# epic2.net
KiCad netlist of a schematic drawn in EAGLE
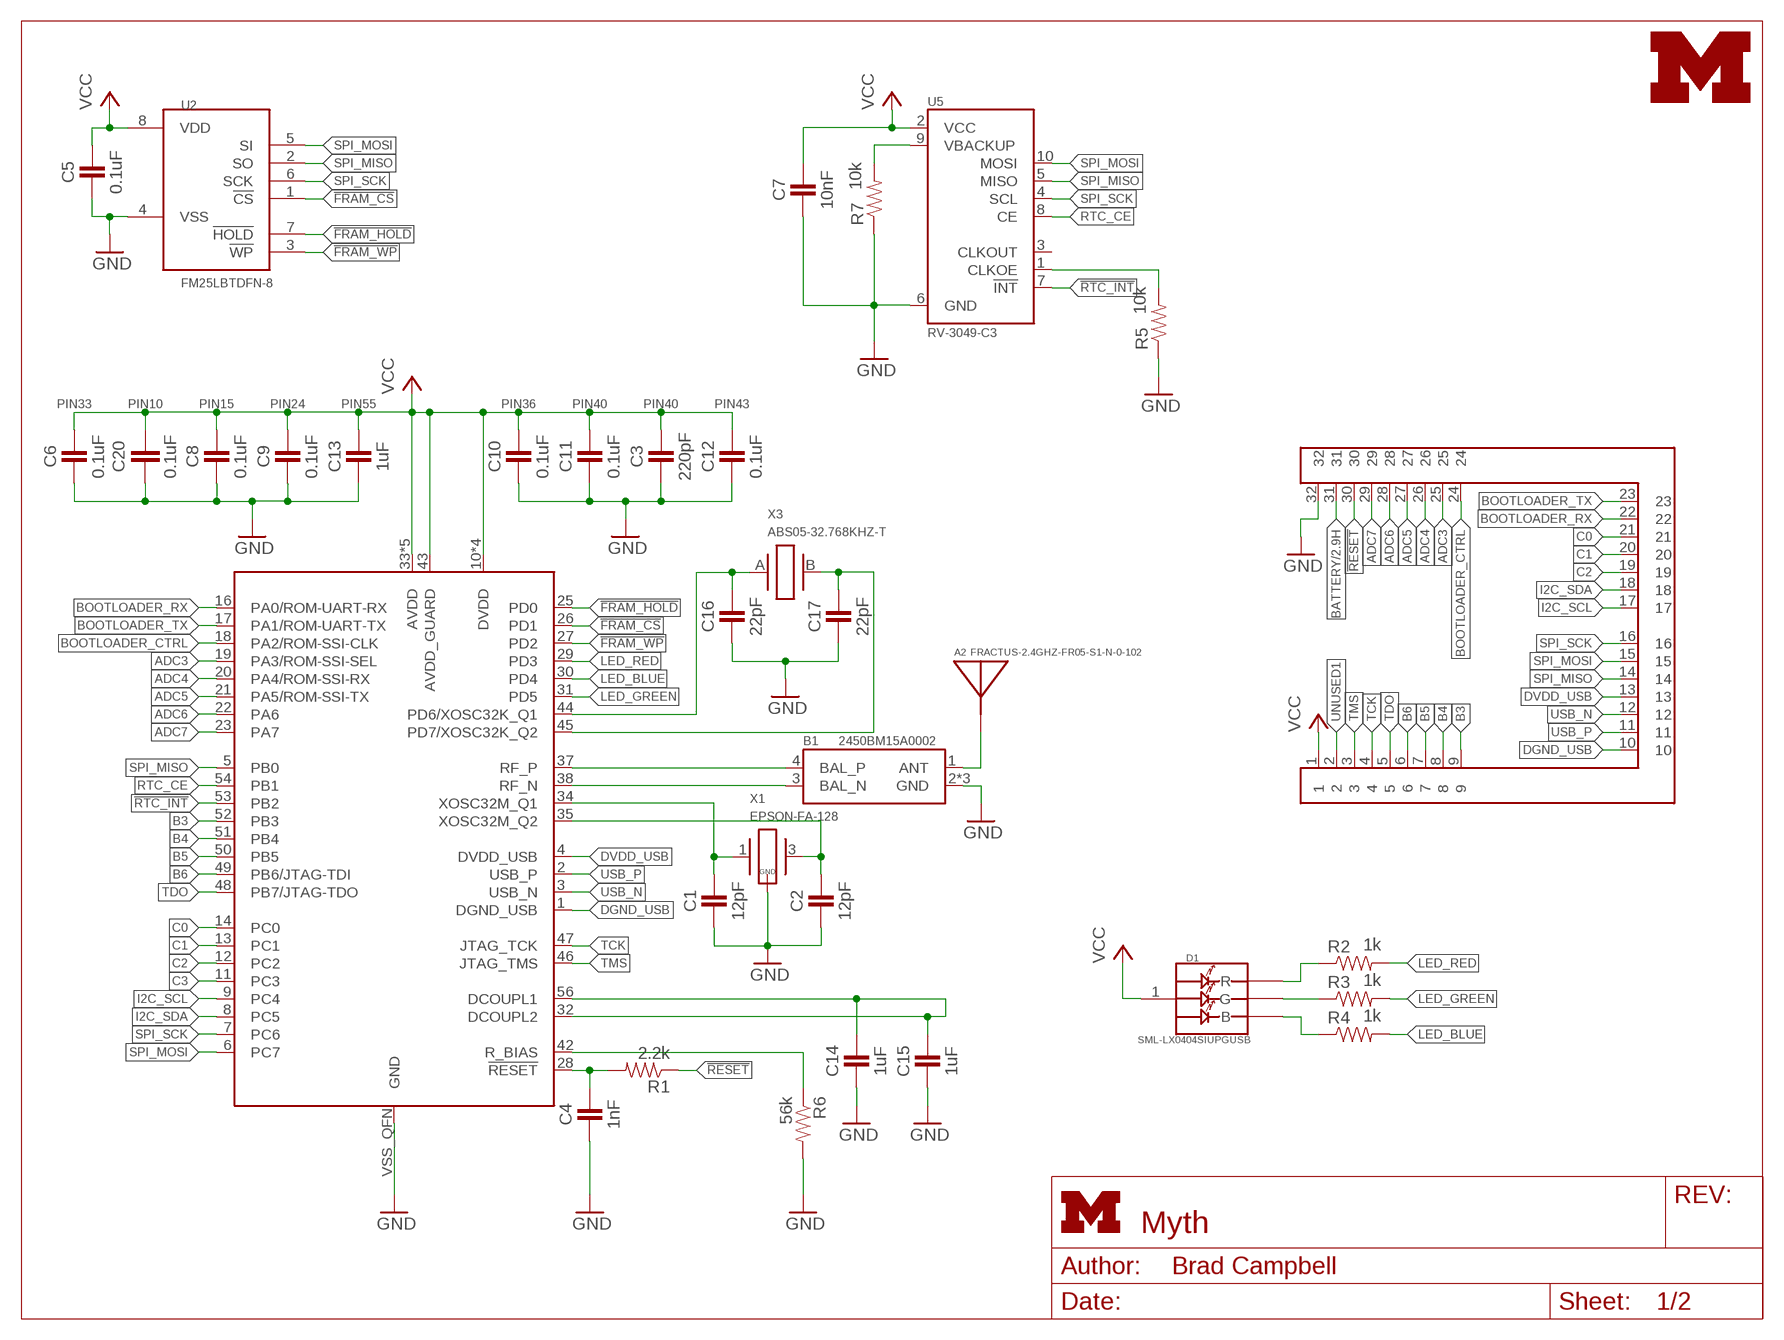
[diagram p0: schematic, sheet 1]
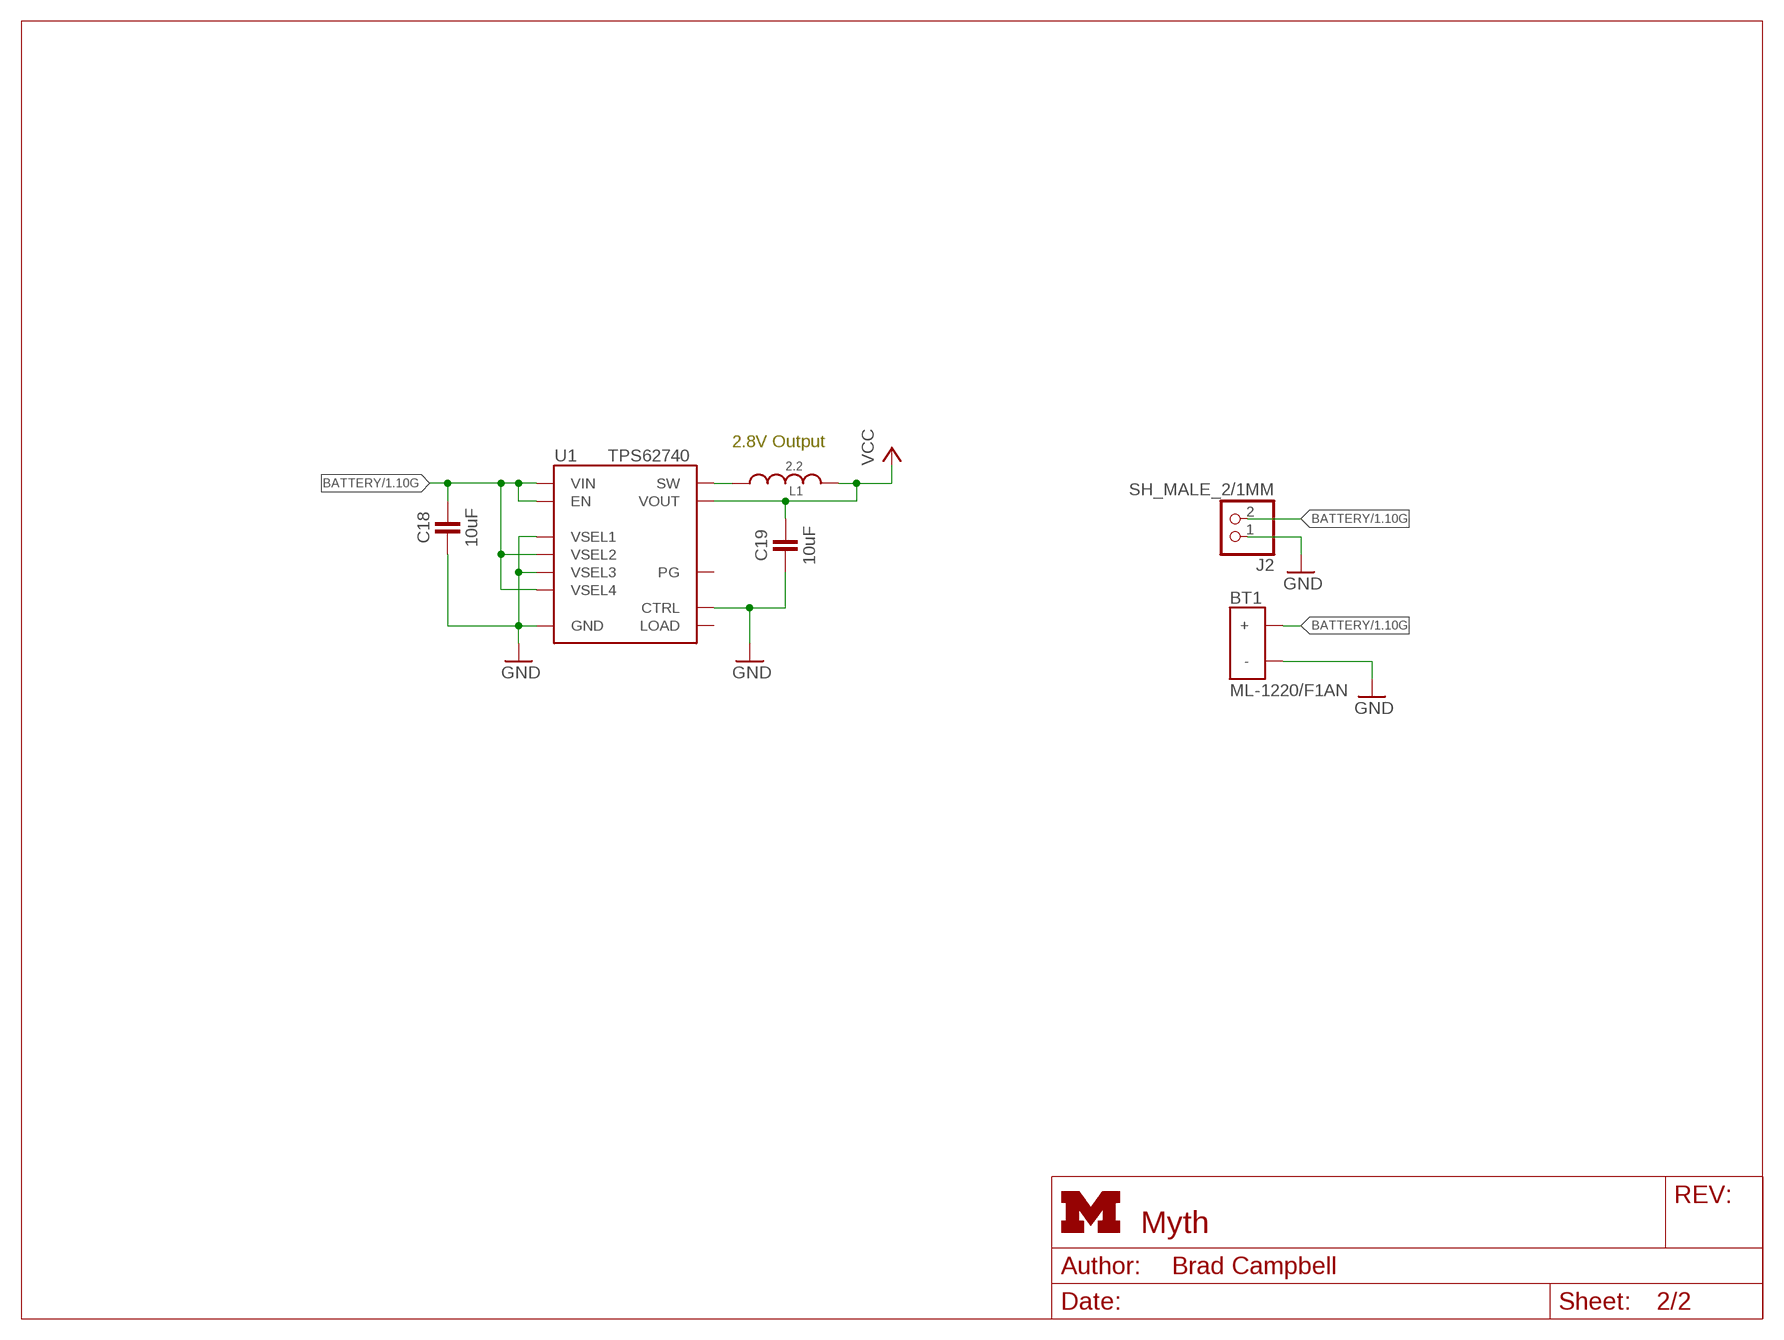
[diagram p1: schematic, sheet 2]

(export (version "E")
  (design (tool "Eeschema 10.0.6"))
  (components
    (comp (ref "A2")
      (value "FRACTUS-2.4GHZ-FR05-S1-N-0-102")
      (footprint "eagle-import:FRACTUS-ANTENNA-FR05-S1-N-0-102")
      (libsource (lib "eagle-import") (part "FRACTUS-2.4GHZ-FR05-S1-N-0-102"))
    )
    (comp (ref "B1")
      (value "2450BM15A0002")
      (footprint "eagle-import:2450BM")
      (libsource (lib "eagle-import") (part "2450BM15A0002"))
    )
    (comp (ref "C1")
      (value "12pF")
      (footprint "eagle-import:0402_CAP")
      (libsource (lib "eagle-import") (part "CAPACITOR"))
    )
    (comp (ref "C2")
      (value "12pF")
      (footprint "eagle-import:0402_CAP")
      (libsource (lib "eagle-import") (part "CAPACITOR"))
    )
    (comp (ref "C3")
      (value "220pF")
      (footprint "eagle-import:0402_CAP")
      (libsource (lib "eagle-import") (part "CAPACITOR"))
    )
    (comp (ref "C4")
      (value "1nF")
      (footprint "eagle-import:0402_CAP")
      (libsource (lib "eagle-import") (part "CAPACITOR"))
    )
    (comp (ref "C5")
      (value "0.1uF")
      (footprint "eagle-import:0402_CAP")
      (libsource (lib "eagle-import") (part "CAPACITOR"))
    )
    (comp (ref "C6")
      (value "0.1uF")
      (footprint "eagle-import:0402_CAP")
      (libsource (lib "eagle-import") (part "CAPACITOR"))
    )
    (comp (ref "C7")
      (value "10nF")
      (footprint "eagle-import:0402_CAP")
      (libsource (lib "eagle-import") (part "CAPACITOR"))
    )
    (comp (ref "C8")
      (value "0.1uF")
      (footprint "eagle-import:0402_CAP")
      (libsource (lib "eagle-import") (part "CAPACITOR"))
    )
    (comp (ref "C9")
      (value "0.1uF")
      (footprint "eagle-import:0402_CAP")
      (libsource (lib "eagle-import") (part "CAPACITOR"))
    )
    (comp (ref "C10")
      (value "0.1uF")
      (footprint "eagle-import:0402_CAP")
      (libsource (lib "eagle-import") (part "CAPACITOR"))
    )
    (comp (ref "C11")
      (value "0.1uF")
      (footprint "eagle-import:0402_CAP")
      (libsource (lib "eagle-import") (part "CAPACITOR"))
    )
    (comp (ref "C12")
      (value "0.1uF")
      (footprint "eagle-import:0402_CAP")
      (libsource (lib "eagle-import") (part "CAPACITOR"))
    )
    (comp (ref "C13")
      (value "1uF")
      (footprint "eagle-import:0402_CAP")
      (libsource (lib "eagle-import") (part "CAPACITOR"))
    )
    (comp (ref "C14")
      (value "1uF")
      (footprint "eagle-import:0402_CAP")
      (libsource (lib "eagle-import") (part "CAPACITOR"))
    )
    (comp (ref "C15")
      (value "1uF")
      (footprint "eagle-import:0402_CAP")
      (libsource (lib "eagle-import") (part "CAPACITOR"))
    )
    (comp (ref "C16")
      (value "22pF")
      (footprint "eagle-import:0402_CAP")
      (libsource (lib "eagle-import") (part "CAPACITOR"))
    )
    (comp (ref "C17")
      (value "22pF")
      (footprint "eagle-import:0402_CAP")
      (libsource (lib "eagle-import") (part "CAPACITOR"))
    )
    (comp (ref "C20")
      (value "0.1uF")
      (footprint "eagle-import:C0201")
      (libsource (lib "eagle-import") (part "C-EUC0201"))
    )
    (comp (ref "D1")
      (value "SML-LX0404SIUPGUSB")
      (footprint "eagle-import:1MM_SQ_4PAD")
      (libsource (lib "eagle-import") (part "SML-LX0404SIUPGUSB"))
    )
    (comp (ref "J1")
      (value "EPIC2-HEADER2")
      (footprint "eagle-import:EPIC2-HEADER2")
      (libsource (lib "eagle-import") (part "EPIC2-HEADER2"))
    )
    (comp (ref "LOGO1")
      (value "UMICH_SOLID_TINY")
      (footprint "eagle-import:UMICH_SOLID_50MIL")
      (libsource (lib "eagle-import") (part "UMICH_SOLID_TINY"))
    )
    (comp (ref "R1")
      (value "2.2k")
      (footprint "eagle-import:0402_RES")
      (libsource (lib "eagle-import") (part "RESISTOR"))
    )
    (comp (ref "R2")
      (value "1k")
      (footprint "eagle-import:0402_RES")
      (libsource (lib "eagle-import") (part "RESISTOR"))
    )
    (comp (ref "R3")
      (value "1k")
      (footprint "eagle-import:0402_RES")
      (libsource (lib "eagle-import") (part "RESISTOR"))
    )
    (comp (ref "R4")
      (value "1k")
      (footprint "eagle-import:0402_RES")
      (libsource (lib "eagle-import") (part "RESISTOR"))
    )
    (comp (ref "R5")
      (value "10k")
      (footprint "eagle-import:0402_RES")
      (libsource (lib "eagle-import") (part "RESISTOR"))
    )
    (comp (ref "R6")
      (value "56k")
      (footprint "eagle-import:0402_RES")
      (libsource (lib "eagle-import") (part "RESISTOR"))
    )
    (comp (ref "R7")
      (value "10k")
      (footprint "eagle-import:0402_RES")
      (libsource (lib "eagle-import") (part "RESISTOR"))
    )
    (comp (ref "U2")
      (value "FM25LBTDFN-8")
      (footprint "eagle-import:TDFN-8")
      (libsource (lib "eagle-import") (part "FM25LBTDFN-8"))
    )
    (comp (ref "U3")
      (value "CC2538")
      (footprint "eagle-import:S-PVQFN-N56")
      (libsource (lib "eagle-import") (part "CC2538"))
    )
    (comp (ref "U5")
      (value "RV-3049-C3")
      (footprint "eagle-import:MICRO-CRYSTAL-C3")
      (libsource (lib "eagle-import") (part "RV-3049-C3"))
    )
    (comp (ref "X1")
      (value "EPSON-FA-128")
      (footprint "eagle-import:FA-128")
      (libsource (lib "eagle-import") (part "EPSON-FA-128"))
    )
    (comp (ref "X3")
      (value "ABS05-32.768KHZ-T")
      (footprint "eagle-import:ABS05")
      (libsource (lib "eagle-import") (part "ABS05-32.768KHZ-T"))
    )
    (comp (ref "BT1")
      (value "ML-1220/F1AN")
      (footprint "eagle-import:ML-1220_F1BN")
      (libsource (lib "eagle-import") (part "ML-1220/F1AN"))
    )
    (comp (ref "C18")
      (value "10uF")
      (footprint "eagle-import:0603_CAP")
      (libsource (lib "eagle-import") (part "CAPACITOR0603_CAP"))
    )
    (comp (ref "C19")
      (value "10uF")
      (footprint "eagle-import:0603_CAP")
      (libsource (lib "eagle-import") (part "CAPACITOR0603_CAP"))
    )
    (comp (ref "J2")
      (value "SH_MALE_2/1MM")
      (footprint "eagle-import:SH-1X2_1MM")
      (libsource (lib "eagle-import") (part "SH_MALE_2/1MM"))
    )
    (comp (ref "L1")
      (value "2.2")
      (footprint "eagle-import:MIPSZ201D")
      (libsource (lib "eagle-import") (part "MIPSZ2012D"))
    )
    (comp (ref "U1")
      (value "TPS62740")
      (footprint "eagle-import:R-PWSON-12")
      (libsource (lib "eagle-import") (part "TPS62740"))
    )
  )
  (nets
    (net (code "1") (name "ADC3") (class "Default")
      (node (ref "J1") (pin "25") (pinfunction "25_25") (pintype "bidirectional"))
      (node (ref "U3") (pin "19") (pinfunction "PA3/ROM-SSI-SEL_19") (pintype "bidirectional"))
    )
    (net (code "2") (name "ADC4") (class "Default")
      (node (ref "J1") (pin "26") (pinfunction "26_26") (pintype "bidirectional"))
      (node (ref "U3") (pin "20") (pinfunction "PA4/ROM-SSI-RX_20") (pintype "bidirectional"))
    )
    (net (code "3") (name "ADC5") (class "Default")
      (node (ref "J1") (pin "27") (pinfunction "27_27") (pintype "bidirectional"))
      (node (ref "U3") (pin "21") (pinfunction "PA5/ROM-SSI-TX_21") (pintype "bidirectional"))
    )
    (net (code "4") (name "ADC6") (class "Default")
      (node (ref "J1") (pin "28") (pinfunction "28_28") (pintype "bidirectional"))
      (node (ref "U3") (pin "22") (pinfunction "PA6_22") (pintype "bidirectional"))
    )
    (net (code "5") (name "ADC7") (class "Default")
      (node (ref "J1") (pin "29") (pinfunction "29_29") (pintype "bidirectional"))
      (node (ref "U3") (pin "23") (pinfunction "PA7_23") (pintype "bidirectional"))
    )
    (net (code "6") (name "B3") (class "Default")
      (node (ref "J1") (pin "9") (pinfunction "9_9") (pintype "bidirectional"))
      (node (ref "U3") (pin "52") (pinfunction "PB3_52") (pintype "bidirectional"))
    )
    (net (code "7") (name "B4") (class "Default")
      (node (ref "J1") (pin "8") (pinfunction "8_8") (pintype "bidirectional"))
      (node (ref "U3") (pin "51") (pinfunction "PB4_51") (pintype "bidirectional"))
    )
    (net (code "8") (name "B5") (class "Default")
      (node (ref "J1") (pin "7") (pinfunction "7_7") (pintype "bidirectional"))
      (node (ref "U3") (pin "50") (pinfunction "PB5_50") (pintype "bidirectional"))
    )
    (net (code "9") (name "B6") (class "Default")
      (node (ref "J1") (pin "6") (pinfunction "6_6") (pintype "bidirectional"))
      (node (ref "U3") (pin "49") (pinfunction "PB6/JTAG-TDI_49") (pintype "bidirectional"))
    )
    (net (code "10") (name "BATTERY") (class "Default")
      (node (ref "BT1") (pin "POS") (pinfunction "+_POS") (pintype "bidirectional"))
      (node (ref "C18") (pin "1") (pinfunction "1_1") (pintype "bidirectional"))
      (node (ref "J1") (pin "31") (pinfunction "31_31") (pintype "bidirectional"))
      (node (ref "J2") (pin "2") (pinfunction "2_2") (pintype "passive"))
      (node (ref "U1") (pin "1") (pinfunction "VIN_1") (pintype "bidirectional"))
      (node (ref "U1") (pin "10") (pinfunction "VSEL2_10") (pintype "bidirectional"))
      (node (ref "U1") (pin "12") (pinfunction "EN_12") (pintype "bidirectional"))
      (node (ref "U1") (pin "8") (pinfunction "VSEL4_8") (pintype "bidirectional"))
    )
    (net (code "11") (name "BOOTLOADER_CTRL") (class "Default")
      (node (ref "J1") (pin "24") (pinfunction "24_24") (pintype "bidirectional"))
      (node (ref "U3") (pin "18") (pinfunction "PA2/ROM-SSI-CLK_18") (pintype "bidirectional"))
    )
    (net (code "12") (name "BOOTLOADER_RX") (class "Default")
      (node (ref "J1") (pin "22") (pinfunction "22_22") (pintype "bidirectional"))
      (node (ref "U3") (pin "16") (pinfunction "PA0/ROM-UART-RX_16") (pintype "bidirectional"))
    )
    (net (code "13") (name "BOOTLOADER_TX") (class "Default")
      (node (ref "J1") (pin "23") (pinfunction "23_23") (pintype "bidirectional"))
      (node (ref "U3") (pin "17") (pinfunction "PA1/ROM-UART-TX_17") (pintype "bidirectional"))
    )
    (net (code "14") (name "C0") (class "Default")
      (node (ref "J1") (pin "21") (pinfunction "21_21") (pintype "bidirectional"))
      (node (ref "U3") (pin "14") (pinfunction "PC0_14") (pintype "bidirectional"))
    )
    (net (code "15") (name "C1") (class "Default")
      (node (ref "J1") (pin "20") (pinfunction "20_20") (pintype "bidirectional"))
      (node (ref "U3") (pin "13") (pinfunction "PC1_13") (pintype "bidirectional"))
    )
    (net (code "16") (name "C2") (class "Default")
      (node (ref "J1") (pin "19") (pinfunction "19_19") (pintype "bidirectional"))
      (node (ref "U3") (pin "12") (pinfunction "PC2_12") (pintype "bidirectional"))
    )
    (net (code "17") (name "C3") (class "Default")
      (node (ref "U3") (pin "11") (pinfunction "PC3_11") (pintype "bidirectional"))
    )
    (net (code "18") (name "DGND_USB") (class "Default")
      (node (ref "J1") (pin "10") (pinfunction "10_10") (pintype "bidirectional"))
      (node (ref "U3") (pin "1") (pinfunction "DGND_USB_1") (pintype "bidirectional"))
    )
    (net (code "19") (name "DVDD_USB") (class "Default")
      (node (ref "J1") (pin "13") (pinfunction "13_13") (pintype "bidirectional"))
      (node (ref "U3") (pin "4") (pinfunction "DVDD_USB_4") (pintype "bidirectional"))
    )
    (net (code "20") (name "GND") (class "Default")
      (node (ref "B1") (pin "2") (pinfunction "GND_2") (pintype "bidirectional"))
      (node (ref "B1") (pin "5") (pinfunction "GND_5") (pintype "bidirectional"))
      (node (ref "B1") (pin "6") (pinfunction "GND_6") (pintype "bidirectional"))
      (node (ref "BT1") (pin "NEG") (pinfunction "-_NEG") (pintype "bidirectional"))
      (node (ref "C1") (pin "2") (pinfunction "2_2") (pintype "bidirectional"))
      (node (ref "C10") (pin "2") (pinfunction "2_2") (pintype "bidirectional"))
      (node (ref "C11") (pin "2") (pinfunction "2_2") (pintype "bidirectional"))
      (node (ref "C12") (pin "2") (pinfunction "2_2") (pintype "bidirectional"))
      (node (ref "C13") (pin "2") (pinfunction "2_2") (pintype "bidirectional"))
      (node (ref "C14") (pin "2") (pinfunction "2_2") (pintype "bidirectional"))
      (node (ref "C15") (pin "2") (pinfunction "2_2") (pintype "bidirectional"))
      (node (ref "C16") (pin "2") (pinfunction "2_2") (pintype "bidirectional"))
      (node (ref "C17") (pin "2") (pinfunction "2_2") (pintype "bidirectional"))
      (node (ref "C18") (pin "2") (pinfunction "2_2") (pintype "bidirectional"))
      (node (ref "C19") (pin "2") (pinfunction "2_2") (pintype "bidirectional"))
      (node (ref "C2") (pin "2") (pinfunction "2_2") (pintype "bidirectional"))
      (node (ref "C20") (pin "2") (pinfunction "2_2") (pintype "passive"))
      (node (ref "C3") (pin "2") (pinfunction "2_2") (pintype "bidirectional"))
      (node (ref "C4") (pin "2") (pinfunction "2_2") (pintype "bidirectional"))
      (node (ref "C5") (pin "2") (pinfunction "2_2") (pintype "bidirectional"))
      (node (ref "C6") (pin "2") (pinfunction "2_2") (pintype "bidirectional"))
      (node (ref "C7") (pin "2") (pinfunction "2_2") (pintype "bidirectional"))
      (node (ref "C8") (pin "2") (pinfunction "2_2") (pintype "bidirectional"))
      (node (ref "C9") (pin "2") (pinfunction "2_2") (pintype "bidirectional"))
      (node (ref "J1") (pin "32") (pinfunction "32_32") (pintype "bidirectional"))
      (node (ref "J2") (pin "1") (pinfunction "1_1") (pintype "passive"))
      (node (ref "R5") (pin "1") (pinfunction "1_1") (pintype "passive"))
      (node (ref "R6") (pin "2") (pinfunction "2_2") (pintype "passive"))
      (node (ref "R7") (pin "1") (pinfunction "1_1") (pintype "passive"))
      (node (ref "U1") (pin "11") (pinfunction "VSEL1_11") (pintype "bidirectional"))
      (node (ref "U1") (pin "3") (pinfunction "GND_3") (pintype "bidirectional"))
      (node (ref "U1") (pin "4") (pinfunction "CTRL_4") (pintype "bidirectional"))
      (node (ref "U1") (pin "9") (pinfunction "VSEL3_9") (pintype "bidirectional"))
      (node (ref "U1") (pin "NC") (pinfunction "GND_NC") (pintype "bidirectional"))
      (node (ref "U2") (pin "4") (pinfunction "VSS_4") (pintype "bidirectional"))
      (node (ref "U3") (pin "VSS_QFN") (pinfunction "GND_VSS_QFN") (pintype "bidirectional"))
      (node (ref "U5") (pin "6") (pinfunction "GND_6") (pintype "bidirectional"))
      (node (ref "X1") (pin "2") (pinfunction "GND_2") (pintype "bidirectional"))
      (node (ref "X1") (pin "4") (pinfunction "GND_4") (pintype "bidirectional"))
    )
    (net (code "21") (name "I2C_SCL") (class "Default")
      (node (ref "J1") (pin "17") (pinfunction "17_17") (pintype "bidirectional"))
      (node (ref "U3") (pin "9") (pinfunction "PC4_9") (pintype "bidirectional"))
    )
    (net (code "22") (name "I2C_SDA") (class "Default")
      (node (ref "J1") (pin "18") (pinfunction "18_18") (pintype "bidirectional"))
      (node (ref "U3") (pin "8") (pinfunction "PC5_8") (pintype "bidirectional"))
    )
    (net (code "23") (name "LED_BLUE") (class "Default")
      (node (ref "R4") (pin "2") (pinfunction "2_2") (pintype "passive"))
      (node (ref "U3") (pin "30") (pinfunction "PD4_30") (pintype "bidirectional"))
    )
    (net (code "24") (name "LED_GREEN") (class "Default")
      (node (ref "R3") (pin "2") (pinfunction "2_2") (pintype "passive"))
      (node (ref "U3") (pin "31") (pinfunction "PD5_31") (pintype "bidirectional"))
    )
    (net (code "25") (name "LED_RED") (class "Default")
      (node (ref "R2") (pin "2") (pinfunction "2_2") (pintype "passive"))
      (node (ref "U3") (pin "29") (pinfunction "PD3_29") (pintype "bidirectional"))
    )
    (net (code "26") (name "Net-(A2-ANTENNA)") (class "Default")
      (node (ref "A2") (pin "1") (pinfunction "ANTENNA_1") (pintype "bidirectional"))
      (node (ref "B1") (pin "1") (pinfunction "ANT_1") (pintype "bidirectional"))
    )
    (net (code "27") (name "Net-(B1-BAL_N)") (class "Default")
      (node (ref "B1") (pin "3") (pinfunction "BAL_N_3") (pintype "bidirectional"))
      (node (ref "U3") (pin "38") (pinfunction "RF_N_38") (pintype "bidirectional"))
    )
    (net (code "28") (name "Net-(B1-BAL_P)") (class "Default")
      (node (ref "B1") (pin "4") (pinfunction "BAL_P_4") (pintype "bidirectional"))
      (node (ref "U3") (pin "37") (pinfunction "RF_P_37") (pintype "bidirectional"))
    )
    (net (code "29") (name "Net-(D1-B)") (class "Default")
      (node (ref "D1") (pin "3") (pinfunction "B_3") (pintype "output"))
      (node (ref "R4") (pin "1") (pinfunction "1_1") (pintype "passive"))
    )
    (net (code "30") (name "Net-(D1-G)") (class "Default")
      (node (ref "D1") (pin "4") (pinfunction "G_4") (pintype "output"))
      (node (ref "R3") (pin "1") (pinfunction "1_1") (pintype "passive"))
    )
    (net (code "31") (name "Net-(D1-R)") (class "Default")
      (node (ref "D1") (pin "2") (pinfunction "R_2") (pintype "output"))
      (node (ref "R2") (pin "1") (pinfunction "1_1") (pintype "passive"))
    )
    (net (code "32") (name "Net-(U1-SW)") (class "Default")
      (node (ref "L1") (pin "1") (pinfunction "1_1") (pintype "bidirectional"))
      (node (ref "U1") (pin "2") (pinfunction "SW_2") (pintype "bidirectional"))
    )
    (net (code "33") (name "Net-(U3-DCOUPL1)") (class "Default")
      (node (ref "C14") (pin "1") (pinfunction "1_1") (pintype "bidirectional"))
      (node (ref "C15") (pin "1") (pinfunction "1_1") (pintype "bidirectional"))
      (node (ref "U3") (pin "32") (pinfunction "DCOUPL2_32") (pintype "bidirectional"))
      (node (ref "U3") (pin "56") (pinfunction "DCOUPL1_56") (pintype "bidirectional"))
    )
    (net (code "34") (name "Net-(U3-PD6{slash}XOSC32K_Q1)") (class "Default")
      (node (ref "C16") (pin "1") (pinfunction "1_1") (pintype "bidirectional"))
      (node (ref "U3") (pin "44") (pinfunction "PD6/XOSC32K_Q1_44") (pintype "bidirectional"))
      (node (ref "X3") (pin "A") (pinfunction "1_A") (pintype "bidirectional"))
    )
    (net (code "35") (name "Net-(U3-PD7{slash}XOSC32K_Q2)") (class "Default")
      (node (ref "C17") (pin "1") (pinfunction "1_1") (pintype "bidirectional"))
      (node (ref "U3") (pin "45") (pinfunction "PD7/XOSC32K_Q2_45") (pintype "bidirectional"))
      (node (ref "X3") (pin "B") (pinfunction "2_B") (pintype "bidirectional"))
    )
    (net (code "36") (name "Net-(U3-R_BIAS)") (class "Default")
      (node (ref "R6") (pin "1") (pinfunction "1_1") (pintype "passive"))
      (node (ref "U3") (pin "42") (pinfunction "R_BIAS_42") (pintype "bidirectional"))
    )
    (net (code "37") (name "Net-(U3-XOSC32M_Q1)") (class "Default")
      (node (ref "C1") (pin "1") (pinfunction "1_1") (pintype "bidirectional"))
      (node (ref "U3") (pin "34") (pinfunction "XOSC32M_Q1_34") (pintype "bidirectional"))
      (node (ref "X1") (pin "1") (pinfunction "1_1") (pintype "bidirectional"))
    )
    (net (code "38") (name "Net-(U3-XOSC32M_Q2)") (class "Default")
      (node (ref "C2") (pin "1") (pinfunction "1_1") (pintype "bidirectional"))
      (node (ref "U3") (pin "35") (pinfunction "XOSC32M_Q2_35") (pintype "bidirectional"))
      (node (ref "X1") (pin "3") (pinfunction "2_3") (pintype "bidirectional"))
    )
    (net (code "39") (name "Net-(U3-~{RESET})") (class "Default")
      (node (ref "C4") (pin "1") (pinfunction "1_1") (pintype "bidirectional"))
      (node (ref "R1") (pin "2") (pinfunction "2_2") (pintype "passive"))
      (node (ref "U3") (pin "28") (pinfunction "~{RESET}_28") (pintype "bidirectional"))
    )
    (net (code "40") (name "Net-(U5-CLKOE)") (class "Default")
      (node (ref "R5") (pin "2") (pinfunction "2_2") (pintype "passive"))
      (node (ref "U5") (pin "1") (pinfunction "CLKOE_1") (pintype "bidirectional"))
    )
    (net (code "41") (name "Net-(U5-VBACKUP)") (class "Default")
      (node (ref "R7") (pin "2") (pinfunction "2_2") (pintype "passive"))
      (node (ref "U5") (pin "9") (pinfunction "VBACKUP_9") (pintype "bidirectional"))
    )
    (net (code "42") (name "RTC_CE") (class "Default")
      (node (ref "U3") (pin "54") (pinfunction "PB1_54") (pintype "bidirectional"))
      (node (ref "U5") (pin "8") (pinfunction "CE_8") (pintype "bidirectional"))
    )
    (net (code "43") (name "SPI_MISO") (class "Default")
      (node (ref "J1") (pin "14") (pinfunction "14_14") (pintype "bidirectional"))
      (node (ref "U2") (pin "2") (pinfunction "SO_2") (pintype "bidirectional"))
      (node (ref "U3") (pin "5") (pinfunction "PB0_5") (pintype "bidirectional"))
      (node (ref "U5") (pin "5") (pinfunction "MISO_5") (pintype "bidirectional"))
    )
    (net (code "44") (name "SPI_MOSI") (class "Default")
      (node (ref "J1") (pin "15") (pinfunction "15_15") (pintype "bidirectional"))
      (node (ref "U2") (pin "5") (pinfunction "SI_5") (pintype "bidirectional"))
      (node (ref "U3") (pin "6") (pinfunction "PC7_6") (pintype "bidirectional"))
      (node (ref "U5") (pin "10") (pinfunction "MOSI_10") (pintype "bidirectional"))
    )
    (net (code "45") (name "SPI_SCK") (class "Default")
      (node (ref "J1") (pin "16") (pinfunction "16_16") (pintype "bidirectional"))
      (node (ref "U2") (pin "6") (pinfunction "SCK_6") (pintype "bidirectional"))
      (node (ref "U3") (pin "7") (pinfunction "PC6_7") (pintype "bidirectional"))
      (node (ref "U5") (pin "4") (pinfunction "SCL_4") (pintype "bidirectional"))
    )
    (net (code "46") (name "TCK") (class "Default")
      (node (ref "J1") (pin "4") (pinfunction "4_4") (pintype "bidirectional"))
      (node (ref "U3") (pin "47") (pinfunction "JTAG_TCK_47") (pintype "bidirectional"))
    )
    (net (code "47") (name "TDO") (class "Default")
      (node (ref "J1") (pin "5") (pinfunction "5_5") (pintype "bidirectional"))
      (node (ref "U3") (pin "48") (pinfunction "PB7/JTAG-TDO_48") (pintype "bidirectional"))
    )
    (net (code "48") (name "TMS") (class "Default")
      (node (ref "J1") (pin "3") (pinfunction "3_3") (pintype "bidirectional"))
      (node (ref "U3") (pin "46") (pinfunction "JTAG_TMS_46") (pintype "bidirectional"))
    )
    (net (code "49") (name "UNUSED1") (class "Default")
      (node (ref "J1") (pin "2") (pinfunction "2_2") (pintype "bidirectional"))
    )
    (net (code "50") (name "USB_N") (class "Default")
      (node (ref "J1") (pin "12") (pinfunction "12_12") (pintype "bidirectional"))
      (node (ref "U3") (pin "3") (pinfunction "USB_N_3") (pintype "bidirectional"))
    )
    (net (code "51") (name "USB_P") (class "Default")
      (node (ref "J1") (pin "11") (pinfunction "11_11") (pintype "bidirectional"))
      (node (ref "U3") (pin "2") (pinfunction "USB_P_2") (pintype "bidirectional"))
    )
    (net (code "52") (name "VCC") (class "Default")
      (node (ref "C10") (pin "1") (pinfunction "1_1") (pintype "bidirectional"))
      (node (ref "C11") (pin "1") (pinfunction "1_1") (pintype "bidirectional"))
      (node (ref "C12") (pin "1") (pinfunction "1_1") (pintype "bidirectional"))
      (node (ref "C13") (pin "1") (pinfunction "1_1") (pintype "bidirectional"))
      (node (ref "C19") (pin "1") (pinfunction "1_1") (pintype "bidirectional"))
      (node (ref "C20") (pin "1") (pinfunction "1_1") (pintype "passive"))
      (node (ref "C3") (pin "1") (pinfunction "1_1") (pintype "bidirectional"))
      (node (ref "C5") (pin "1") (pinfunction "1_1") (pintype "bidirectional"))
      (node (ref "C6") (pin "1") (pinfunction "1_1") (pintype "bidirectional"))
      (node (ref "C7") (pin "1") (pinfunction "1_1") (pintype "bidirectional"))
      (node (ref "C8") (pin "1") (pinfunction "1_1") (pintype "bidirectional"))
      (node (ref "C9") (pin "1") (pinfunction "1_1") (pintype "bidirectional"))
      (node (ref "D1") (pin "1") (pinfunction "VDD_1") (pintype "bidirectional"))
      (node (ref "J1") (pin "1") (pinfunction "1_1") (pintype "bidirectional"))
      (node (ref "L1") (pin "2") (pinfunction "2_2") (pintype "bidirectional"))
      (node (ref "U1") (pin "5") (pinfunction "VOUT_5") (pintype "bidirectional"))
      (node (ref "U2") (pin "8") (pinfunction "VDD_8") (pintype "bidirectional"))
      (node (ref "U3") (pin "10") (pinfunction "DVDD_10") (pintype "bidirectional"))
      (node (ref "U3") (pin "15") (pinfunction "DVDD_15") (pintype "bidirectional"))
      (node (ref "U3") (pin "24") (pinfunction "DVDD_24") (pintype "bidirectional"))
      (node (ref "U3") (pin "33") (pinfunction "AVDD_33") (pintype "bidirectional"))
      (node (ref "U3") (pin "36") (pinfunction "AVDD_36") (pintype "bidirectional"))
      (node (ref "U3") (pin "39") (pinfunction "AVDD_39") (pintype "bidirectional"))
      (node (ref "U3") (pin "40") (pinfunction "AVDD_40") (pintype "bidirectional"))
      (node (ref "U3") (pin "41") (pinfunction "AVDD_41") (pintype "bidirectional"))
      (node (ref "U3") (pin "43") (pinfunction "AVDD_GUARD_43") (pintype "bidirectional"))
      (node (ref "U3") (pin "55") (pinfunction "DVDD_55") (pintype "bidirectional"))
      (node (ref "U5") (pin "2") (pinfunction "VCC_2") (pintype "bidirectional"))
    )
    (net (code "53") (name "unconnected-(U1-LOAD-Pad6)") (class "Default")
      (node (ref "U1") (pin "6") (pinfunction "LOAD_6") (pintype "bidirectional"))
    )
    (net (code "54") (name "unconnected-(U1-PG-Pad7)") (class "Default")
      (node (ref "U1") (pin "7") (pinfunction "PG_7") (pintype "bidirectional"))
    )
    (net (code "55") (name "unconnected-(U5-CLKOUT-Pad3)") (class "Default")
      (node (ref "U5") (pin "3") (pinfunction "CLKOUT_3") (pintype "bidirectional"))
    )
    (net (code "56") (name "~{FRAM_CS}") (class "Default")
      (node (ref "U2") (pin "1") (pinfunction "~{CS}_1") (pintype "bidirectional"))
      (node (ref "U3") (pin "26") (pinfunction "PD1_26") (pintype "bidirectional"))
    )
    (net (code "57") (name "~{FRAM_HOLD}") (class "Default")
      (node (ref "U2") (pin "7") (pinfunction "~{HOLD}_7") (pintype "bidirectional"))
      (node (ref "U3") (pin "25") (pinfunction "PD0_25") (pintype "bidirectional"))
    )
    (net (code "58") (name "~{FRAM_WP}") (class "Default")
      (node (ref "U2") (pin "3") (pinfunction "~{WP}_3") (pintype "bidirectional"))
      (node (ref "U3") (pin "27") (pinfunction "PD2_27") (pintype "bidirectional"))
    )
    (net (code "59") (name "~{RESET}") (class "Default")
      (node (ref "J1") (pin "30") (pinfunction "30_30") (pintype "bidirectional"))
      (node (ref "R1") (pin "1") (pinfunction "1_1") (pintype "passive"))
    )
    (net (code "60") (name "~{RTC_INT}") (class "Default")
      (node (ref "U3") (pin "53") (pinfunction "PB2_53") (pintype "bidirectional"))
      (node (ref "U5") (pin "7") (pinfunction "~{INT}_7") (pintype "bidirectional"))
    )
  )
)
